# Sheet_Robo_Hand_main.net
KiCad netlist of a schematic drawn in Altium Designer
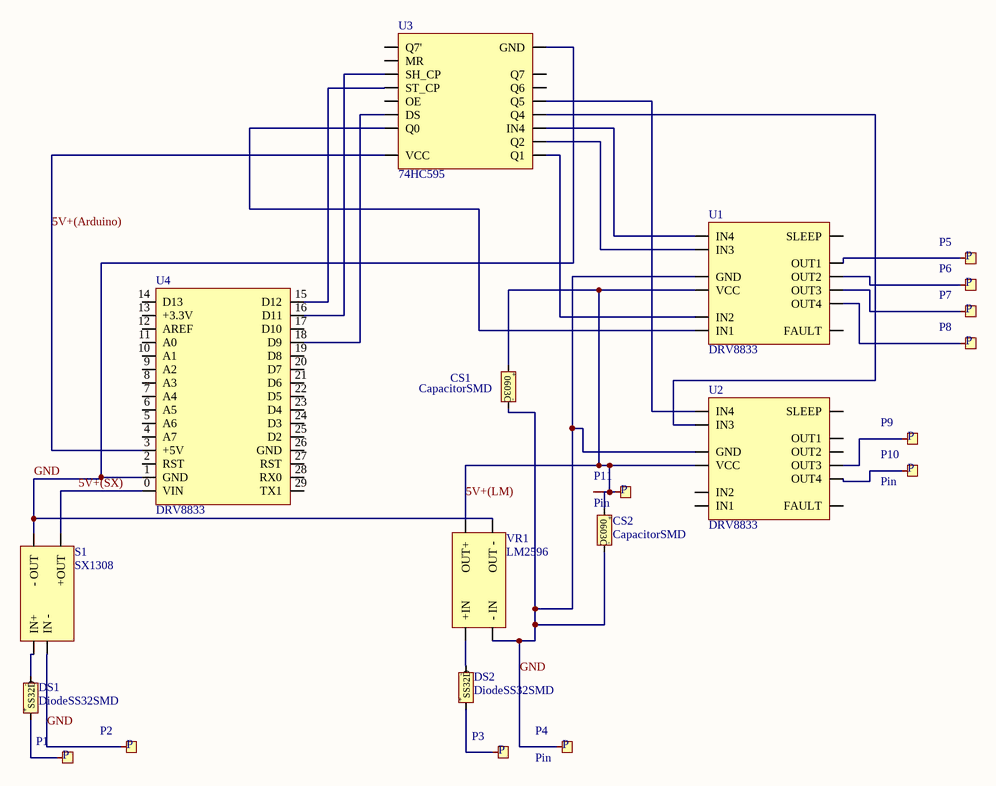
[diagram p0: Sheet_Robo_Hand_main.SchDoc]

(export (version "E")
  (design (tool "Eeschema 10.0.6"))
  (components
    (comp (ref "CS1")
      (value "CapacitorSMD")
      (footprint "CapacitorSMD")
      (libsource (lib "CapacitorSMD0603") (part "CapacitorSMD"))
    )
    (comp (ref "CS2")
      (value "CapacitorSMD")
      (footprint "CapacitorSMD")
      (libsource (lib "CapacitorSMD0603") (part "CapacitorSMD"))
    )
    (comp (ref "DS1")
      (value "DiodeSS32SMD")
      (footprint "DiodeSS32SMD")
      (libsource (lib "DiodeSS32") (part "DiodeSS32SMD"))
    )
    (comp (ref "DS2")
      (value "DiodeSS32SMD")
      (footprint "DiodeSS32SMD")
      (libsource (lib "DiodeSS32") (part "DiodeSS32SMD"))
    )
    (comp (ref "P1") (value "Pin") (footprint "P") (libsource (lib "Pin") (part "Pin")))
    (comp (ref "P2") (value "Pin") (footprint "P") (libsource (lib "Pin") (part "Pin")))
    (comp (ref "P3") (value "Pin") (footprint "P") (libsource (lib "Pin") (part "Pin")))
    (comp (ref "P4") (value "Pin") (footprint "P") (libsource (lib "Pin") (part "Pin")))
    (comp (ref "P5") (value "Pin") (footprint "P") (libsource (lib "Pin") (part "Pin")))
    (comp (ref "P6") (value "Pin") (footprint "P") (libsource (lib "Pin") (part "Pin")))
    (comp (ref "P7") (value "Pin") (footprint "P") (libsource (lib "Pin") (part "Pin")))
    (comp (ref "P8") (value "Pin") (footprint "P") (libsource (lib "Pin") (part "Pin")))
    (comp (ref "P9") (value "Pin") (footprint "P") (libsource (lib "Pin") (part "Pin")))
    (comp (ref "P10") (value "Pin") (footprint "P") (libsource (lib "Pin") (part "Pin")))
    (comp (ref "P11") (value "Pin") (footprint "P") (libsource (lib "Pin") (part "Pin")))
    (comp (ref "S1")
      (value "SX1308")
      (footprint "DC-DC Step-Up Footprint")
      (libsource (lib "Sch_SX1308F") (part "SX1308"))
    )
    (comp (ref "U1")
      (value "DRV8833")
      (footprint "PCB_DRV8833")
      (description "Драйвер крокового/колекторних двигунів DRV8833")
      (libsource (lib "Sch_DRV8833") (part "Motor Driver"))
    )
    (comp (ref "U2")
      (value "DRV8833")
      (footprint "PCB_DRV8833")
      (description "Драйвер крокового/колекторних двигунів DRV8833")
      (libsource (lib "PCB_Robo_Hand") (part "Motor Driver"))
    )
    (comp (ref "U3")
      (value "74HC595")
      (footprint "PCB_74HC595_Footprint")
      (description "SN74HC595N - вихідний зсувний регістр 74HC595")
      (libsource (lib "Sch74HC595") (part "SCS-16"))
    )
    (comp (ref "U4")
      (value "DRV8833")
      (footprint "PCB_ATMega328p")
      (description "DCCduino Nano CH340 - аналог Arduino Nano v3.0 TYPE C")
      (libsource (lib "PCB_Robo_Hand") (part "Arduino Nano"))
    )
    (comp (ref "VR1")
      (value "LM2596")
      (footprint "DC-DC Step-Down Footprint")
      (description "DC-DC конвертер знижуючий 4.5...40В на 1.5...35В на LM2596")
      (libsource (lib "Sch_LM2596F") (part "DC-DC Step-Down"))
    )
  )
  (nets
    (net (code "1") (name "/5V+(Arduino)") (class "Default")
      (node (ref "U3") (pin "8") (pinfunction "VCC_8") (pintype "power_in"))
      (node (ref "U4") (pin "3") (pinfunction "+5V_3") (pintype "passive"))
    )
    (net (code "2") (name "/5V+(LM)") (class "Default")
      (node (ref "CS1") (pin "0") (pinfunction "+_0") (pintype "passive"))
      (node (ref "CS2") (pin "0") (pinfunction "+_0") (pintype "passive"))
      (node (ref "P11") (pin "0") (pinfunction "*_0") (pintype "passive"))
      (node (ref "U1") (pin "2") (pinfunction "VCC_2") (pintype "power_in"))
      (node (ref "U2") (pin "2") (pinfunction "VCC_2") (pintype "power_in"))
      (node (ref "VR1") (pin "2") (pinfunction "OUT+_2") (pintype "power_in"))
    )
    (net (code "3") (name "/5V+(SX)") (class "Default")
      (node (ref "S1") (pin "0") (pinfunction "+OUT_0") (pintype "power_in"))
      (node (ref "U4") (pin "0") (pinfunction "VIN_0") (pintype "passive"))
    )
    (net (code "4") (name "/GND") (class "Default")
      (node (ref "CS1") (pin "1") (pinfunction "-_1") (pintype "passive"))
      (node (ref "CS2") (pin "1") (pinfunction "-_1") (pintype "passive"))
      (node (ref "P2") (pin "0") (pinfunction "*_0") (pintype "passive"))
      (node (ref "P4") (pin "0") (pinfunction "*_0") (pintype "passive"))
      (node (ref "S1") (pin "1") (pinfunction "-_OUT_1") (pintype "power_in"))
      (node (ref "S1") (pin "2") (pinfunction "IN_-_2") (pintype "power_in"))
      (node (ref "U1") (pin "3") (pinfunction "GND_3") (pintype "power_in"))
      (node (ref "U2") (pin "3") (pinfunction "GND_3") (pintype "power_in"))
      (node (ref "U3") (pin "0") (pinfunction "GND_0") (pintype "power_in"))
      (node (ref "U4") (pin "1") (pinfunction "GND_1") (pintype "passive"))
      (node (ref "VR1") (pin "1") (pinfunction "-_IN_1") (pintype "power_in"))
      (node (ref "VR1") (pin "3") (pinfunction "OUT_-_3") (pintype "power_in"))
    )
    (net (code "5") (name "Net-(DS1-+)") (class "Default")
      (node (ref "DS1") (pin "0") (pinfunction "+_0") (pintype "passive"))
      (node (ref "P1") (pin "0") (pinfunction "*_0") (pintype "passive"))
    )
    (net (code "6") (name "Net-(DS1--)") (class "Default")
      (node (ref "DS1") (pin "1") (pinfunction "-_1") (pintype "passive"))
      (node (ref "S1") (pin "3") (pinfunction "IN+_3") (pintype "power_in"))
    )
    (net (code "7") (name "Net-(DS2-+)") (class "Default")
      (node (ref "DS2") (pin "0") (pinfunction "+_0") (pintype "passive"))
      (node (ref "P3") (pin "0") (pinfunction "*_0") (pintype "passive"))
    )
    (net (code "8") (name "Net-(DS2--)") (class "Default")
      (node (ref "DS2") (pin "1") (pinfunction "-_1") (pintype "passive"))
      (node (ref "VR1") (pin "0") (pinfunction "+IN_0") (pintype "power_in"))
    )
    (net (code "9") (name "Net-(P5-*)") (class "Default")
      (node (ref "P5") (pin "0") (pinfunction "*_0") (pintype "passive"))
      (node (ref "U1") (pin "7") (pinfunction "OUT1_7") (pintype "passive"))
    )
    (net (code "10") (name "Net-(P6-*)") (class "Default")
      (node (ref "P6") (pin "0") (pinfunction "*_0") (pintype "passive"))
      (node (ref "U1") (pin "8") (pinfunction "OUT2_8") (pintype "passive"))
    )
    (net (code "11") (name "Net-(P7-*)") (class "Default")
      (node (ref "P7") (pin "0") (pinfunction "*_0") (pintype "passive"))
      (node (ref "U1") (pin "9") (pinfunction "OUT3_9") (pintype "passive"))
    )
    (net (code "12") (name "Net-(P8-*)") (class "Default")
      (node (ref "P8") (pin "0") (pinfunction "*_0") (pintype "passive"))
      (node (ref "U1") (pin "10") (pinfunction "OUT4_10") (pintype "passive"))
    )
    (net (code "13") (name "Net-(P9-*)") (class "Default")
      (node (ref "P9") (pin "0") (pinfunction "*_0") (pintype "passive"))
      (node (ref "U2") (pin "9") (pinfunction "OUT3_9") (pintype "passive"))
    )
    (net (code "14") (name "Net-(P10-*)") (class "Default")
      (node (ref "P10") (pin "0") (pinfunction "*_0") (pintype "passive"))
      (node (ref "U2") (pin "10") (pinfunction "OUT4_10") (pintype "passive"))
    )
    (net (code "15") (name "Net-(U1-IN1)") (class "Default")
      (node (ref "U1") (pin "0") (pinfunction "IN1_0") (pintype "passive"))
      (node (ref "U3") (pin "9") (pinfunction "Q0_9") (pintype "passive"))
    )
    (net (code "16") (name "Net-(U1-IN2)") (class "Default")
      (node (ref "U1") (pin "1") (pinfunction "IN2_1") (pintype "passive"))
      (node (ref "U3") (pin "7") (pinfunction "Q1_7") (pintype "passive"))
    )
    (net (code "17") (name "Net-(U1-IN3)") (class "Default")
      (node (ref "U1") (pin "4") (pinfunction "IN3_4") (pintype "passive"))
      (node (ref "U3") (pin "6") (pinfunction "Q2_6") (pintype "passive"))
    )
    (net (code "18") (name "Net-(U1-IN4)") (class "Default")
      (node (ref "U1") (pin "5") (pinfunction "IN4_5") (pintype "passive"))
      (node (ref "U3") (pin "5") (pinfunction "IN4_5") (pintype "passive"))
    )
    (net (code "19") (name "Net-(U2-IN3)") (class "Default")
      (node (ref "U2") (pin "4") (pinfunction "IN3_4") (pintype "passive"))
      (node (ref "U3") (pin "4") (pinfunction "Q4_4") (pintype "passive"))
    )
    (net (code "20") (name "Net-(U2-IN4)") (class "Default")
      (node (ref "U2") (pin "5") (pinfunction "IN4_5") (pintype "passive"))
      (node (ref "U3") (pin "3") (pinfunction "Q5_3") (pintype "passive"))
    )
    (net (code "21") (name "Net-(U3-DS)") (class "Default")
      (node (ref "U3") (pin "10") (pinfunction "DS_10") (pintype "passive"))
      (node (ref "U4") (pin "18") (pinfunction "D9_18") (pintype "passive"))
    )
    (net (code "22") (name "Net-(U3-SH_CP)") (class "Default")
      (node (ref "U3") (pin "13") (pinfunction "SH_CP_13") (pintype "passive"))
      (node (ref "U4") (pin "16") (pinfunction "D11_16") (pintype "passive"))
    )
    (net (code "23") (name "Net-(U3-ST_CP)") (class "Default")
      (node (ref "U3") (pin "12") (pinfunction "ST_CP_12") (pintype "passive"))
      (node (ref "U4") (pin "15") (pinfunction "D12_15") (pintype "passive"))
    )
    (net (code "24") (name "unconnected-(U1-FAULT-Pad11)") (class "Default")
      (node (ref "U1") (pin "11") (pinfunction "FAULT_11") (pintype "passive"))
    )
    (net (code "25") (name "unconnected-(U1-SLEEP-Pad6)") (class "Default")
      (node (ref "U1") (pin "6") (pinfunction "SLEEP_6") (pintype "passive"))
    )
    (net (code "26") (name "unconnected-(U2-FAULT-Pad11)") (class "Default")
      (node (ref "U2") (pin "11") (pinfunction "FAULT_11") (pintype "passive"))
    )
    (net (code "27") (name "unconnected-(U2-IN1-Pad0)") (class "Default")
      (node (ref "U2") (pin "0") (pinfunction "IN1_0") (pintype "passive"))
    )
    (net (code "28") (name "unconnected-(U2-IN2-Pad1)") (class "Default")
      (node (ref "U2") (pin "1") (pinfunction "IN2_1") (pintype "passive"))
    )
    (net (code "29") (name "unconnected-(U2-OUT1-Pad7)") (class "Default")
      (node (ref "U2") (pin "7") (pinfunction "OUT1_7") (pintype "passive"))
    )
    (net (code "30") (name "unconnected-(U2-OUT2-Pad8)") (class "Default")
      (node (ref "U2") (pin "8") (pinfunction "OUT2_8") (pintype "passive"))
    )
    (net (code "31") (name "unconnected-(U2-SLEEP-Pad6)") (class "Default")
      (node (ref "U2") (pin "6") (pinfunction "SLEEP_6") (pintype "passive"))
    )
    (net (code "32") (name "unconnected-(U3-MR-Pad14)") (class "Default")
      (node (ref "U3") (pin "14") (pinfunction "MR_14") (pintype "passive"))
    )
    (net (code "33") (name "unconnected-(U3-OE-Pad11)") (class "Default")
      (node (ref "U3") (pin "11") (pinfunction "OE_11") (pintype "passive"))
    )
    (net (code "34") (name "unconnected-(U3-Q6-Pad2)") (class "Default")
      (node (ref "U3") (pin "2") (pinfunction "Q6_2") (pintype "passive"))
    )
    (net (code "35") (name "unconnected-(U3-Q7'-Pad15)") (class "Default")
      (node (ref "U3") (pin "15") (pinfunction "Q7'_15") (pintype "passive"))
    )
    (net (code "36") (name "unconnected-(U3-Q7-Pad1)") (class "Default")
      (node (ref "U3") (pin "1") (pinfunction "Q7_1") (pintype "passive"))
    )
    (net (code "37") (name "unconnected-(U4-+3.3V-Pad13)") (class "Default")
      (node (ref "U4") (pin "13") (pinfunction "+3.3V_13") (pintype "passive"))
    )
    (net (code "38") (name "unconnected-(U4-A0-Pad11)") (class "Default")
      (node (ref "U4") (pin "11") (pinfunction "A0_11") (pintype "passive"))
    )
    (net (code "39") (name "unconnected-(U4-A1-Pad10)") (class "Default")
      (node (ref "U4") (pin "10") (pinfunction "A1_10") (pintype "passive"))
    )
    (net (code "40") (name "unconnected-(U4-A2-Pad9)") (class "Default")
      (node (ref "U4") (pin "9") (pinfunction "A2_9") (pintype "passive"))
    )
    (net (code "41") (name "unconnected-(U4-A3-Pad8)") (class "Default")
      (node (ref "U4") (pin "8") (pinfunction "A3_8") (pintype "passive"))
    )
    (net (code "42") (name "unconnected-(U4-A4-Pad7)") (class "Default")
      (node (ref "U4") (pin "7") (pinfunction "A4_7") (pintype "passive"))
    )
    (net (code "43") (name "unconnected-(U4-A5-Pad6)") (class "Default")
      (node (ref "U4") (pin "6") (pinfunction "A5_6") (pintype "passive"))
    )
    (net (code "44") (name "unconnected-(U4-A6-Pad5)") (class "Default")
      (node (ref "U4") (pin "5") (pinfunction "A6_5") (pintype "passive"))
    )
    (net (code "45") (name "unconnected-(U4-A7-Pad4)") (class "Default")
      (node (ref "U4") (pin "4") (pinfunction "A7_4") (pintype "passive"))
    )
    (net (code "46") (name "unconnected-(U4-AREF-Pad12)") (class "Default")
      (node (ref "U4") (pin "12") (pinfunction "AREF_12") (pintype "passive"))
    )
    (net (code "47") (name "unconnected-(U4-D2-Pad25)") (class "Default")
      (node (ref "U4") (pin "25") (pinfunction "D2_25") (pintype "passive"))
    )
    (net (code "48") (name "unconnected-(U4-D3-Pad24)") (class "Default")
      (node (ref "U4") (pin "24") (pinfunction "D3_24") (pintype "passive"))
    )
    (net (code "49") (name "unconnected-(U4-D4-Pad23)") (class "Default")
      (node (ref "U4") (pin "23") (pinfunction "D4_23") (pintype "passive"))
    )
    (net (code "50") (name "unconnected-(U4-D5-Pad22)") (class "Default")
      (node (ref "U4") (pin "22") (pinfunction "D5_22") (pintype "passive"))
    )
    (net (code "51") (name "unconnected-(U4-D6-Pad21)") (class "Default")
      (node (ref "U4") (pin "21") (pinfunction "D6_21") (pintype "passive"))
    )
    (net (code "52") (name "unconnected-(U4-D7-Pad20)") (class "Default")
      (node (ref "U4") (pin "20") (pinfunction "D7_20") (pintype "passive"))
    )
    (net (code "53") (name "unconnected-(U4-D8-Pad19)") (class "Default")
      (node (ref "U4") (pin "19") (pinfunction "D8_19") (pintype "passive"))
    )
    (net (code "54") (name "unconnected-(U4-D10-Pad17)") (class "Default")
      (node (ref "U4") (pin "17") (pinfunction "D10_17") (pintype "passive"))
    )
    (net (code "55") (name "unconnected-(U4-D13-Pad14)") (class "Default")
      (node (ref "U4") (pin "14") (pinfunction "D13_14") (pintype "passive"))
    )
    (net (code "56") (name "unconnected-(U4-GND-Pad26)") (class "Default")
      (node (ref "U4") (pin "26") (pinfunction "GND_26") (pintype "passive"))
    )
    (net (code "57") (name "unconnected-(U4-RST-Pad2)") (class "Default")
      (node (ref "U4") (pin "2") (pinfunction "RST_2") (pintype "passive"))
    )
    (net (code "58") (name "unconnected-(U4-RST-Pad27)") (class "Default")
      (node (ref "U4") (pin "27") (pinfunction "RST_27") (pintype "passive"))
    )
    (net (code "59") (name "unconnected-(U4-RX0-Pad28)") (class "Default")
      (node (ref "U4") (pin "28") (pinfunction "RX0_28") (pintype "passive"))
    )
    (net (code "60") (name "unconnected-(U4-TX1-Pad29)") (class "Default")
      (node (ref "U4") (pin "29") (pinfunction "TX1_29") (pintype "passive"))
    )
  )
)
